# TOP.net
KiCad netlist of a schematic drawn in Altium Designer
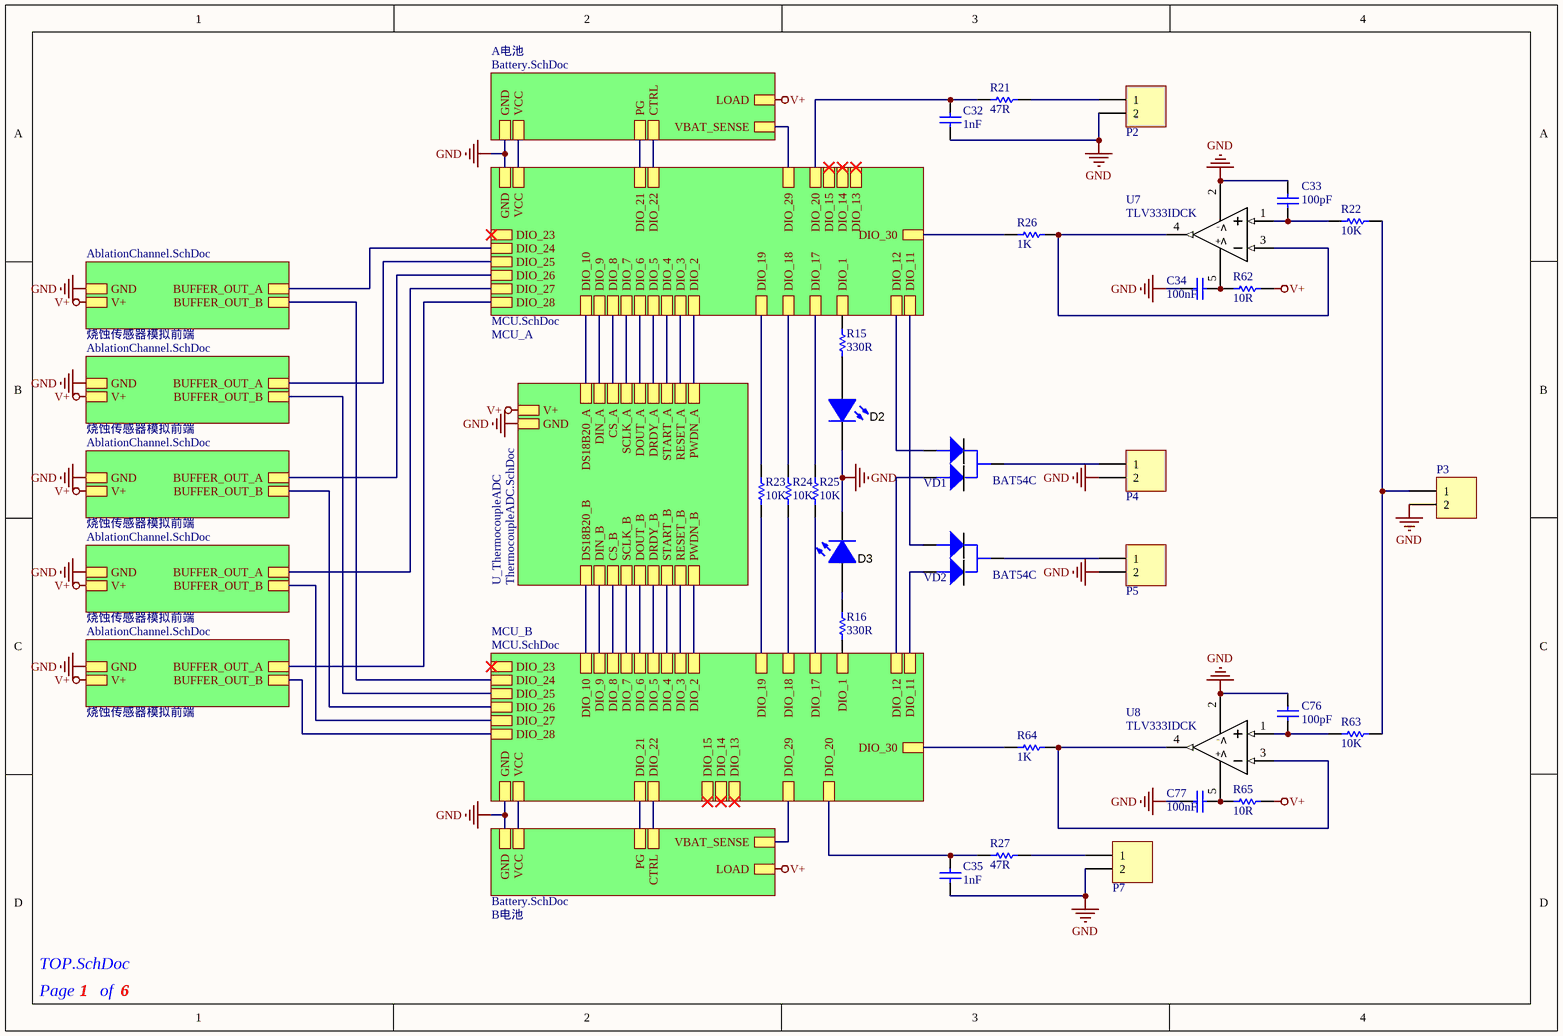
[diagram p0: TOP.SchDoc]

(export (version "E")
  (design (tool "Eeschema 10.0.6"))
  (components
    (comp (ref "C32")
      (value "1nF")
      (footprint "R0603_C")
      (description "精度 ±5% \r\n容值 1nF \r\n额定电压 50V \r\n温漂系数（介质材料) C0G")
      (libsource (lib "00Lib") (part "1nF/0603/50V"))
    )
    (comp (ref "C33")
      (value "100pF")
      (footprint "R0603_C")
      (description "精度 ±5% \r\n容值 100pF \r\n额定电压 50V \r\n温漂系数（介质材料) C0G")
      (libsource (lib "00Lib") (part "100pF/0603/50V"))
    )
    (comp (ref "C34")
      (value "100nF")
      (footprint "R0603_C")
      (description "精度 ±10% \r\n容值 100nF \r\n额定电压 50V \r\n温漂系数（介质材料) X7R")
      (libsource (lib "00Lib") (part "100nF/0603/50V"))
    )
    (comp (ref "C35")
      (value "1nF")
      (footprint "R0603_C")
      (description "精度 ±5% \r\n容值 1nF \r\n额定电压 50V \r\n温漂系数（介质材料) C0G")
      (libsource (lib "00Lib") (part "1nF/0603/50V"))
    )
    (comp (ref "C76")
      (value "100pF")
      (footprint "R0603_C")
      (description "精度 ±5% \r\n容值 100pF \r\n额定电压 50V \r\n温漂系数（介质材料) C0G")
      (libsource (lib "00Lib") (part "100pF/0603/50V"))
    )
    (comp (ref "C77")
      (value "100nF")
      (footprint "R0603_C")
      (description "精度 ±10% \r\n容值 100nF \r\n额定电压 50V \r\n温漂系数（介质材料) X7R")
      (libsource (lib "00Lib") (part "100nF/0603/50V"))
    )
    (comp (ref "D2")
      (value "MHT192WDT-C2")
      (footprint "LED_0603_RED")
      (libsource (lib "00Lib") (part "MHT192WDT-C2"))
    )
    (comp (ref "D3")
      (value "MHT192WDT-C2")
      (footprint "LED_0603_RED")
      (libsource (lib "00Lib") (part "MHT192WDT-C2"))
    )
    (comp (ref "P2")
      (value "Header 2")
      (footprint "CP1X2")
      (description "Header, 2-Pin")
      (libsource (lib "00Lib") (part "Header 2"))
    )
    (comp (ref "P3")
      (value "Header 2")
      (footprint "CP1X2")
      (description "Header, 2-Pin")
      (libsource (lib "00Lib") (part "Header 2"))
    )
    (comp (ref "P4")
      (value "Header 2")
      (footprint "CP1X2")
      (description "Header, 2-Pin")
      (libsource (lib "00Lib") (part "Header 2"))
    )
    (comp (ref "P5")
      (value "Header 2")
      (footprint "CP1X2")
      (description "Header, 2-Pin")
      (libsource (lib "00Lib") (part "Header 2"))
    )
    (comp (ref "P7")
      (value "Header 2")
      (footprint "CP1X2")
      (description "Header, 2-Pin")
      (libsource (lib "00Lib") (part "Header 2"))
    )
    (comp (ref "R15")
      (value "330R")
      (footprint "R0603_R")
      (description "精度 ±1% \r\n温度系数 ±100ppm/℃ \r\n阻值 330Ω \r\n功率 0.1W")
      (libsource (lib "00Lib") (part "330R/0603"))
    )
    (comp (ref "R16")
      (value "330R")
      (footprint "R0603_R")
      (description "精度 ±1% \r\n温度系数 ±100ppm/℃ \r\n阻值 330Ω \r\n功率 0.1W")
      (libsource (lib "00Lib") (part "330R/0603"))
    )
    (comp (ref "R21")
      (value "47R")
      (footprint "R0603_R")
      (description "精度 ±1% \r\n温度系数 ±100ppm/℃ \r\n阻值 47Ω \r\n功率 0.1W")
      (libsource (lib "00Lib") (part "47R/0603"))
    )
    (comp (ref "R22")
      (value "10K")
      (footprint "R0603_R")
      (description "精度 ±1% \r\n温度系数 ±100ppm/℃ \r\n阻值 10kΩ \r\n功率 0.1W")
      (libsource (lib "00Lib") (part "10K/0603"))
    )
    (comp (ref "R23")
      (value "10K")
      (footprint "R0603_R")
      (description "精度 ±1% \r\n温度系数 ±100ppm/℃ \r\n阻值 10kΩ \r\n功率 0.1W")
      (libsource (lib "00Lib") (part "10K/0603"))
    )
    (comp (ref "R24")
      (value "10K")
      (footprint "R0603_R")
      (description "精度 ±1% \r\n温度系数 ±100ppm/℃ \r\n阻值 10kΩ \r\n功率 0.1W")
      (libsource (lib "00Lib") (part "10K/0603"))
    )
    (comp (ref "R25")
      (value "10K")
      (footprint "R0603_R")
      (description "精度 ±1% \r\n温度系数 ±100ppm/℃ \r\n阻值 10kΩ \r\n功率 0.1W")
      (libsource (lib "00Lib") (part "10K/0603"))
    )
    (comp (ref "R26")
      (value "1K")
      (footprint "R0603_R")
      (description "精度 ±1% \r\n温度系数 ±100ppm/℃ \r\n阻值 1kΩ \r\n功率 0.1W")
      (libsource (lib "00Lib") (part "1K/0603"))
    )
    (comp (ref "R27")
      (value "47R")
      (footprint "R0603_R")
      (description "精度 ±1% \r\n温度系数 ±100ppm/℃ \r\n阻值 47Ω \r\n功率 0.1W")
      (libsource (lib "00Lib") (part "47R/0603"))
    )
    (comp (ref "R62")
      (value "10R")
      (footprint "R0603_R")
      (description "精度 ±1% \r\n阻值 10Ω \r\n温度系数 ±100ppm/℃ \r\n功率 0.1W")
      (libsource (lib "00Lib") (part "10R/0603"))
    )
    (comp (ref "R63")
      (value "10K")
      (footprint "R0603_R")
      (description "精度 ±1% \r\n温度系数 ±100ppm/℃ \r\n阻值 10kΩ \r\n功率 0.1W")
      (libsource (lib "00Lib") (part "10K/0603"))
    )
    (comp (ref "R64")
      (value "1K")
      (footprint "R0603_R")
      (description "精度 ±1% \r\n温度系数 ±100ppm/℃ \r\n阻值 1kΩ \r\n功率 0.1W")
      (libsource (lib "00Lib") (part "1K/0603"))
    )
    (comp (ref "R65")
      (value "10R")
      (footprint "R0603_R")
      (description "精度 ±1% \r\n阻值 10Ω \r\n温度系数 ±100ppm/℃ \r\n功率 0.1W")
      (libsource (lib "00Lib") (part "10R/0603"))
    )
    (comp (ref "U7")
      (value "TLV333IDCK")
      (footprint "DCK0005A_N")
      (description "电源电压 1.8V ~ 5.5V, ±0.9V ~ 2.75V\r\n增益带宽积（GBP） 350kHz \r\n压摆率（SR） 0.16 V/us \r\n工作温度 -40°C ~ 125°C")
      (libsource (lib "00Lib") (part "TLV333IDCK"))
    )
    (comp (ref "U8")
      (value "TLV333IDCK")
      (footprint "DCK0005A_N")
      (description "电源电压 1.8V ~ 5.5V, ±0.9V ~ 2.75V\r\n增益带宽积（GBP） 350kHz \r\n压摆率（SR） 0.16 V/us \r\n工作温度 -40°C ~ 125°C")
      (libsource (lib "00Lib") (part "TLV333IDCK"))
    )
    (comp (ref "VD1")
      (value "BAT54C")
      (footprint "SOT-23(SOT-23-3)")
      (description "共阴极，IF=0.2A,VRRM=30V,VF=0.24V@0.1mA,IR=2uA@25V,trr=5ns,SOT23-3,-55℃～150℃")
      (libsource (lib "00Lib") (part "BAT54C"))
    )
    (comp (ref "VD2")
      (value "BAT54C")
      (footprint "SOT-23(SOT-23-3)")
      (description "共阴极，IF=0.2A,VRRM=30V,VF=0.24V@0.1mA,IR=2uA@25V,trr=5ns,SOT23-3,-55℃～150℃")
      (libsource (lib "00Lib") (part "BAT54C"))
    )
  )
  (nets
    (net (code "17") (name "/DIO_1") (class "Default")
      (node (ref "R15") (pin "2") (pinfunction "2_2") (pintype "passive"))
    )
    (net (code "18") (name "/DIO_1_1") (class "Default")
      (node (ref "R16") (pin "1") (pinfunction "1_1") (pintype "passive"))
    )
    (net (code "33") (name "/DIO_11") (class "Default")
      (node (ref "VD2") (pin "1") (pinfunction "A1_1") (pintype "passive"))
    )
    (net (code "34") (name "/DIO_11_1") (class "Default")
      (node (ref "VD2") (pin "2") (pinfunction "A2_2") (pintype "passive"))
    )
    (net (code "35") (name "/DIO_12") (class "Default")
      (node (ref "VD1") (pin "2") (pinfunction "A2_2") (pintype "passive"))
    )
    (net (code "36") (name "/DIO_12_1") (class "Default")
      (node (ref "VD1") (pin "1") (pinfunction "A1_1") (pintype "passive"))
    )
    (net (code "43") (name "/DIO_17") (class "Default")
      (node (ref "R25") (pin "1") (pinfunction "1_1") (pintype "passive"))
    )
    (net (code "44") (name "/DIO_17_1") (class "Default")
      (node (ref "R25") (pin "2") (pinfunction "2_2") (pintype "passive"))
    )
    (net (code "45") (name "/DIO_18") (class "Default")
      (node (ref "R24") (pin "1") (pinfunction "1_1") (pintype "passive"))
    )
    (net (code "46") (name "/DIO_18_1") (class "Default")
      (node (ref "R24") (pin "2") (pinfunction "2_2") (pintype "passive"))
    )
    (net (code "47") (name "/DIO_19") (class "Default")
      (node (ref "R23") (pin "1") (pinfunction "1_1") (pintype "passive"))
    )
    (net (code "48") (name "/DIO_19_1") (class "Default")
      (node (ref "R23") (pin "2") (pinfunction "2_2") (pintype "passive"))
    )
    (net (code "49") (name "/DIO_20") (class "Default")
      (node (ref "C35") (pin "2") (pinfunction "2_2") (pintype "passive"))
      (node (ref "R27") (pin "1") (pinfunction "1_1") (pintype "passive"))
    )
    (net (code "50") (name "/DIO_20_1") (class "Default")
      (node (ref "C32") (pin "2") (pinfunction "2_2") (pintype "passive"))
      (node (ref "R21") (pin "1") (pinfunction "1_1") (pintype "passive"))
    )
    (net (code "57") (name "/DIO_30") (class "Default")
      (node (ref "R64") (pin "2") (pinfunction "2_2") (pintype "passive"))
    )
    (net (code "58") (name "/DIO_30_1") (class "Default")
      (node (ref "R26") (pin "2") (pinfunction "2_2") (pintype "passive"))
    )
    (net (code "61") (name "GND") (class "Default")
      (node (ref "C32") (pin "1") (pinfunction "1_1") (pintype "passive"))
      (node (ref "C33") (pin "1") (pinfunction "1_1") (pintype "passive"))
      (node (ref "C34") (pin "1") (pinfunction "1_1") (pintype "passive"))
      (node (ref "C35") (pin "1") (pinfunction "1_1") (pintype "passive"))
      (node (ref "C76") (pin "1") (pinfunction "1_1") (pintype "passive"))
      (node (ref "C77") (pin "1") (pinfunction "1_1") (pintype "passive"))
      (node (ref "D2") (pin "2") (pinfunction "K_2") (pintype "passive"))
      (node (ref "D3") (pin "2") (pinfunction "K_2") (pintype "passive"))
      (node (ref "P2") (pin "2") (pinfunction "2_2") (pintype "passive"))
      (node (ref "P3") (pin "2") (pinfunction "2_2") (pintype "passive"))
      (node (ref "P4") (pin "2") (pinfunction "2_2") (pintype "passive"))
      (node (ref "P5") (pin "2") (pinfunction "2_2") (pintype "passive"))
      (node (ref "P7") (pin "2") (pinfunction "2_2") (pintype "passive"))
      (node (ref "U7") (pin "2") (pinfunction "V-_2") (pintype "power_in"))
      (node (ref "U8") (pin "2") (pinfunction "V-_2") (pintype "power_in"))
    )
    (net (code "62") (name "Net-(D2-A)") (class "Default")
      (node (ref "D2") (pin "1") (pinfunction "A_1") (pintype "passive"))
      (node (ref "R15") (pin "1") (pinfunction "1_1") (pintype "passive"))
    )
    (net (code "63") (name "Net-(D3-A)") (class "Default")
      (node (ref "D3") (pin "1") (pinfunction "A_1") (pintype "passive"))
      (node (ref "R16") (pin "2") (pinfunction "2_2") (pintype "passive"))
    )
    (net (code "64") (name "Net-(P2-Pad1)") (class "Default")
      (node (ref "P2") (pin "1") (pinfunction "1_1") (pintype "passive"))
      (node (ref "R21") (pin "2") (pinfunction "2_2") (pintype "passive"))
    )
    (net (code "65") (name "Net-(P3-Pad1)") (class "Default")
      (node (ref "P3") (pin "1") (pinfunction "1_1") (pintype "passive"))
      (node (ref "R22") (pin "1") (pinfunction "1_1") (pintype "passive"))
      (node (ref "R63") (pin "1") (pinfunction "1_1") (pintype "passive"))
    )
    (net (code "66") (name "Net-(P7-Pad1)") (class "Default")
      (node (ref "P7") (pin "1") (pinfunction "1_1") (pintype "passive"))
      (node (ref "R27") (pin "2") (pinfunction "2_2") (pintype "passive"))
    )
    (net (code "67") (name "Net-(U7-IN+)") (class "Default")
      (node (ref "C33") (pin "2") (pinfunction "2_2") (pintype "passive"))
      (node (ref "R22") (pin "2") (pinfunction "2_2") (pintype "passive"))
      (node (ref "U7") (pin "1") (pinfunction "IN+_1") (pintype "input"))
    )
    (net (code "68") (name "Net-(U7-IN-)") (class "Default")
      (node (ref "R26") (pin "1") (pinfunction "1_1") (pintype "passive"))
      (node (ref "U7") (pin "3") (pinfunction "IN-_3") (pintype "input"))
      (node (ref "U7") (pin "4") (pinfunction "OUT_4") (pintype "output"))
    )
    (net (code "69") (name "Net-(U7-V+)") (class "Default")
      (node (ref "C34") (pin "2") (pinfunction "2_2") (pintype "passive"))
      (node (ref "R62") (pin "1") (pinfunction "1_1") (pintype "passive"))
      (node (ref "U7") (pin "5") (pinfunction "V+_5") (pintype "power_in"))
    )
    (net (code "70") (name "Net-(U8-IN+)") (class "Default")
      (node (ref "C76") (pin "2") (pinfunction "2_2") (pintype "passive"))
      (node (ref "R63") (pin "2") (pinfunction "2_2") (pintype "passive"))
      (node (ref "U8") (pin "1") (pinfunction "IN+_1") (pintype "input"))
    )
    (net (code "71") (name "Net-(U8-IN-)") (class "Default")
      (node (ref "R64") (pin "1") (pinfunction "1_1") (pintype "passive"))
      (node (ref "U8") (pin "3") (pinfunction "IN-_3") (pintype "input"))
      (node (ref "U8") (pin "4") (pinfunction "OUT_4") (pintype "output"))
    )
    (net (code "72") (name "Net-(U8-V+)") (class "Default")
      (node (ref "C77") (pin "2") (pinfunction "2_2") (pintype "passive"))
      (node (ref "R65") (pin "1") (pinfunction "1_1") (pintype "passive"))
      (node (ref "U8") (pin "5") (pinfunction "V+_5") (pintype "power_in"))
    )
    (net (code "73") (name "Net-(VD1-K)") (class "Default")
      (node (ref "P4") (pin "1") (pinfunction "1_1") (pintype "passive"))
      (node (ref "VD1") (pin "3") (pinfunction "K_3") (pintype "passive"))
    )
    (net (code "74") (name "Net-(VD2-K)") (class "Default")
      (node (ref "P5") (pin "1") (pinfunction "1_1") (pintype "passive"))
      (node (ref "VD2") (pin "3") (pinfunction "K_3") (pintype "passive"))
    )
    (net (code "75") (name "V+") (class "Default")
      (node (ref "R62") (pin "2") (pinfunction "2_2") (pintype "passive"))
      (node (ref "R65") (pin "2") (pinfunction "2_2") (pintype "passive"))
    )
  )
)
